# USB.net
KiCad netlist of a schematic drawn in Altium Designer
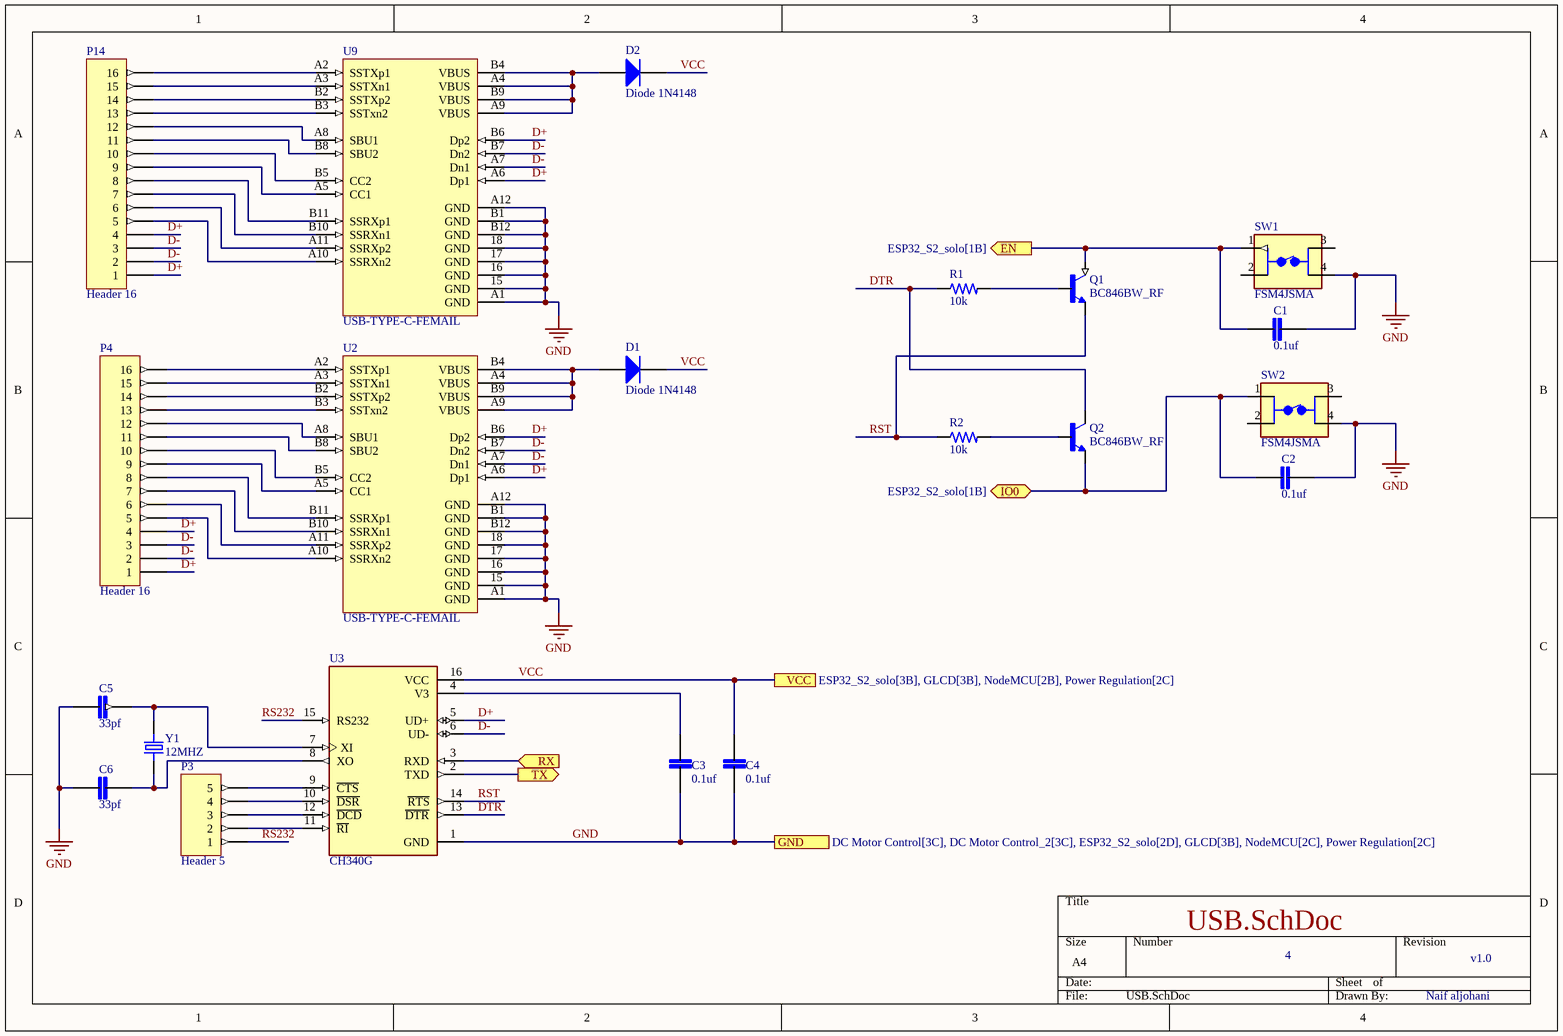
[diagram p0: USB.SchDoc]

(export (version "E")
  (design (tool "Eeschema 10.0.6"))
  (components
    (comp (ref "C1")
      (value "0.1uf")
      (footprint "CAPC2012X140N")
      (description "120PF 100V 10% 0805")
      (fields (field (name "MF") "{'manufacturer': u'AVX'}") (field (name "MP") "LD051A121KAB2A"))
      (libsource (lib "SnapEDA_Library") (part "LD051A121KAB2A"))
    )
    (comp (ref "C2")
      (value "0.1uf")
      (footprint "CAPC2012X140N")
      (description "120PF 100V 10% 0805")
      (fields (field (name "MF") "{'manufacturer': u'AVX'}") (field (name "MP") "LD051A121KAB2A"))
      (libsource (lib "SnapEDA_Library") (part "LD051A121KAB2A"))
    )
    (comp (ref "C3")
      (value "0.1uf")
      (footprint "CAPC2012X140N")
      (description "120PF 100V 10% 0805")
      (fields (field (name "MF") "{'manufacturer': u'AVX'}") (field (name "MP") "LD051A121KAB2A"))
      (libsource (lib "") (part "LD051A121KAB2A_1"))
    )
    (comp (ref "C4")
      (value "0.1uf")
      (footprint "CAPC2012X140N")
      (description "120PF 100V 10% 0805")
      (fields (field (name "MF") "{'manufacturer': u'AVX'}") (field (name "MP") "LD051A121KAB2A"))
      (libsource (lib "") (part "LD051A121KAB2A_1"))
    )
    (comp (ref "C5")
      (value "33pf")
      (footprint "CAPC2012X140N")
      (description "120PF 100V 10% 0805")
      (fields (field (name "MF") "{'manufacturer': u'AVX'}") (field (name "MP") "LD051A121KAB2A"))
      (libsource (lib "") (part "LD051A121KAB2A_3"))
    )
    (comp (ref "C6")
      (value "33pf")
      (footprint "CAPC2012X140N")
      (description "120PF 100V 10% 0805")
      (fields (field (name "MF") "{'manufacturer': u'AVX'}") (field (name "MP") "LD051A121KAB2A"))
      (libsource (lib "") (part "LD051A121KAB2A_2"))
    )
    (comp (ref "D1")
      (value "Diode 1N4148")
      (footprint "DO-35")
      (description "High Conductance Fast Diode")
      (fields (field (name "PUBLISHER") "Altium Limited"))
      (libsource (lib "Miscellaneous Devices") (part "Diode 1N4148"))
    )
    (comp (ref "D2")
      (value "Diode 1N4148")
      (footprint "DO-35")
      (description "High Conductance Fast Diode")
      (fields (field (name "PUBLISHER") "Altium Limited"))
      (libsource (lib "Miscellaneous Devices") (part "Diode 1N4148"))
    )
    (comp (ref "P3")
      (value "Header 5")
      (footprint "HDR1X5")
      (description "Header, 5-Pin")
      (fields (field (name "PUBLISHER") "Altium Limited"))
      (libsource (lib "Miscellaneous Connectors") (part "Header 5"))
    )
    (comp (ref "P4")
      (value "Header 16")
      (footprint "HDR1X16")
      (description "Header, 16-Pin")
      (fields (field (name "PUBLISHER") "Altium Limited"))
      (libsource (lib "Miscellaneous Connectors") (part "Header 16"))
    )
    (comp (ref "P14")
      (value "Header 16")
      (footprint "HDR1X16")
      (description "Header, 16-Pin")
      (fields (field (name "PUBLISHER") "Altium Limited"))
      (libsource (lib "Miscellaneous Connectors") (part "Header 16"))
    )
    (comp (ref "Q1")
      (value "BC846BW_RF")
      (footprint "TRANS_BC846BW_RF")
      (fields (field (name "MF") "{'manufacturer': u'Taiwan Semiconductor'}"))
      (libsource (lib "SnapEDA_Library") (part "BC846BW_RF"))
    )
    (comp (ref "Q2")
      (value "BC846BW_RF")
      (footprint "TRANS_BC846BW_RF")
      (fields (field (name "MF") "{'manufacturer': u'Taiwan Semiconductor'}"))
      (libsource (lib "SnapEDA_Library") (part "BC846BW_RF"))
    )
    (comp (ref "R1")
      (value "10k")
      (footprint "RESC3115X65N")
      (description "RL73H 2B R43 1% 10 RL")
      (fields (field (name "MF") "{'manufacturer': u'TE Connectivity'}") (field (name "MP") "1-1879462-4"))
      (libsource (lib "SnapEDA_Library") (part "1-1879462-4"))
    )
    (comp (ref "R2")
      (value "10k")
      (footprint "RESC3115X65N")
      (description "RL73H 2B R43 1% 10 RL")
      (fields (field (name "MF") "{'manufacturer': u'TE Connectivity'}") (field (name "MP") "1-1879462-4"))
      (libsource (lib "SnapEDA_Library") (part "1-1879462-4"))
    )
    (comp (ref "SW1")
      (value "FSM4JSMA")
      (footprint "TE_FSM4JSMA")
      (description "Switch Tactile OFF (ON) SPST Round Button Gull Wing 0.05A 24VDC 2.6N SMD T/R")
      (fields (field (name "MF") "{'manufacturer': u'TE Connectivity'}"))
      (libsource (lib "SnapEDA_Library") (part "FSM4JSMA"))
    )
    (comp (ref "SW2")
      (value "FSM4JSMA")
      (footprint "TE_FSM4JSMA")
      (description "Switch Tactile OFF (ON) SPST Round Button Gull Wing 0.05A 24VDC 2.6N SMD T/R")
      (fields (field (name "MF") "{'manufacturer': u'TE Connectivity'}"))
      (libsource (lib "SnapEDA_Library") (part "FSM4JSMA"))
    )
    (comp (ref "U2")
      (value "USB-TYPE-C-FEMAIL")
      (footprint "C5156605")
      (libsource (lib "Schlib2") (part "USB-TYPE-C-FEMAIL"))
    )
    (comp (ref "U3")
      (value "CH340G")
      (footprint "SOIC127P600X180-16N")
      (fields (field (name "MF") "{'manufacturer': u'WCH'}"))
      (libsource (lib "SnapEDA_Library") (part "CH340G"))
    )
    (comp (ref "U9")
      (value "USB-TYPE-C-FEMAIL")
      (footprint "C5156605")
      (libsource (lib "Schlib2") (part "USB-TYPE-C-FEMAIL"))
    )
    (comp (ref "Y1")
      (value "12MHZ")
      (footprint "XTAL_ECS-51-S-1")
      (fields (field (name "MF") "{'manufacturer': u'ECS'}") (field (name "MP") "ECS-51-S-1"))
      (libsource (lib "SnapEDA_Library") (part "ECS-51-S-1"))
    )
  )
  (nets
    (net (code "1") (name "/D+") (class "Default")
      (node (ref "P14") (pin "1") (pinfunction "1_1") (pintype "passive"))
      (node (ref "P14") (pin "4") (pinfunction "4_4") (pintype "passive"))
      (node (ref "P4") (pin "1") (pinfunction "1_1") (pintype "passive"))
      (node (ref "P4") (pin "4") (pinfunction "4_4") (pintype "passive"))
      (node (ref "U2") (pin "A6") (pinfunction "Dp1_A6") (pintype "input"))
      (node (ref "U2") (pin "B6") (pinfunction "Dp2_B6") (pintype "input"))
      (node (ref "U3") (pin "5") (pinfunction "UD+_5") (pintype "bidirectional"))
      (node (ref "U9") (pin "A6") (pinfunction "Dp1_A6") (pintype "input"))
      (node (ref "U9") (pin "B6") (pinfunction "Dp2_B6") (pintype "input"))
    )
    (net (code "2") (name "/D-") (class "Default")
      (node (ref "P14") (pin "2") (pinfunction "2_2") (pintype "passive"))
      (node (ref "P14") (pin "3") (pinfunction "3_3") (pintype "passive"))
      (node (ref "P4") (pin "2") (pinfunction "2_2") (pintype "passive"))
      (node (ref "P4") (pin "3") (pinfunction "3_3") (pintype "passive"))
      (node (ref "U2") (pin "A7") (pinfunction "Dn1_A7") (pintype "input"))
      (node (ref "U2") (pin "B7") (pinfunction "Dn2_B7") (pintype "input"))
      (node (ref "U3") (pin "6") (pinfunction "UD-_6") (pintype "bidirectional"))
      (node (ref "U9") (pin "A7") (pinfunction "Dn1_A7") (pintype "input"))
      (node (ref "U9") (pin "B7") (pinfunction "Dn2_B7") (pintype "input"))
    )
    (net (code "3") (name "/DTR") (class "Default")
      (node (ref "Q2") (pin "3") (pinfunction "C_3") (pintype "input"))
      (node (ref "R1") (pin "1") (pinfunction "1_1") (pintype "passive"))
      (node (ref "U3") (pin "13") (pinfunction "~{DTR}_13") (pintype "output"))
    )
    (net (code "4") (name "/EN") (class "Default")
      (node (ref "C1") (pin "1") (pinfunction "1_1") (pintype "passive"))
      (node (ref "Q1") (pin "3") (pinfunction "C_3") (pintype "input"))
      (node (ref "SW1") (pin "1") (pinfunction "1_1") (pintype "output"))
    )
    (net (code "5") (name "/IO0") (class "Default")
      (node (ref "C2") (pin "1") (pinfunction "1_1") (pintype "passive"))
      (node (ref "Q2") (pin "2") (pinfunction "E_2") (pintype "passive"))
      (node (ref "SW2") (pin "1") (pinfunction "1_1") (pintype "output"))
    )
    (net (code "6") (name "/RS232") (class "Default")
      (node (ref "P3") (pin "1") (pinfunction "1_1") (pintype "output"))
      (node (ref "U3") (pin "15") (pinfunction "RS232_15") (pintype "input"))
    )
    (net (code "7") (name "/RST") (class "Default")
      (node (ref "Q1") (pin "2") (pinfunction "E_2") (pintype "passive"))
      (node (ref "R2") (pin "1") (pinfunction "1_1") (pintype "passive"))
      (node (ref "U3") (pin "14") (pinfunction "~{RTS}_14") (pintype "output"))
    )
    (net (code "8") (name "/RX") (class "Default")
      (node (ref "U3") (pin "3") (pinfunction "RXD_3") (pintype "input"))
    )
    (net (code "9") (name "/TX") (class "Default")
      (node (ref "U3") (pin "2") (pinfunction "TXD_2") (pintype "output"))
    )
    (net (code "10") (name "/VCC") (class "Default")
      (node (ref "C4") (pin "2") (pinfunction "2_2") (pintype "passive"))
      (node (ref "D1") (pin "2") (pinfunction "K_2") (pintype "passive"))
      (node (ref "D2") (pin "2") (pinfunction "K_2") (pintype "passive"))
      (node (ref "U3") (pin "16") (pinfunction "VCC_16") (pintype "power_in"))
    )
    (net (code "11") (name "GND") (class "Default")
      (node (ref "C1") (pin "2") (pinfunction "2_2") (pintype "passive"))
      (node (ref "C2") (pin "2") (pinfunction "2_2") (pintype "passive"))
      (node (ref "C3") (pin "1") (pinfunction "1_1") (pintype "passive"))
      (node (ref "C4") (pin "1") (pinfunction "1_1") (pintype "passive"))
      (node (ref "C5") (pin "2") (pinfunction "2_2") (pintype "passive"))
      (node (ref "C6") (pin "2") (pinfunction "2_2") (pintype "passive"))
      (node (ref "SW1") (pin "4") (pinfunction "4_4") (pintype "passive"))
      (node (ref "SW2") (pin "4") (pinfunction "4_4") (pintype "passive"))
      (node (ref "U2") (pin "15") (pinfunction "GND_15") (pintype "power_in"))
      (node (ref "U2") (pin "16") (pinfunction "GND_16") (pintype "power_in"))
      (node (ref "U2") (pin "17") (pinfunction "GND_17") (pintype "power_in"))
      (node (ref "U2") (pin "18") (pinfunction "GND_18") (pintype "power_in"))
      (node (ref "U2") (pin "A1") (pinfunction "GND_A1") (pintype "power_in"))
      (node (ref "U2") (pin "A12") (pinfunction "GND_A12") (pintype "power_in"))
      (node (ref "U2") (pin "B1") (pinfunction "GND_B1") (pintype "power_in"))
      (node (ref "U2") (pin "B12") (pinfunction "GND_B12") (pintype "power_in"))
      (node (ref "U3") (pin "1") (pinfunction "GND_1") (pintype "power_in"))
      (node (ref "U9") (pin "15") (pinfunction "GND_15") (pintype "power_in"))
      (node (ref "U9") (pin "16") (pinfunction "GND_16") (pintype "power_in"))
      (node (ref "U9") (pin "17") (pinfunction "GND_17") (pintype "power_in"))
      (node (ref "U9") (pin "18") (pinfunction "GND_18") (pintype "power_in"))
      (node (ref "U9") (pin "A1") (pinfunction "GND_A1") (pintype "power_in"))
      (node (ref "U9") (pin "A12") (pinfunction "GND_A12") (pintype "power_in"))
      (node (ref "U9") (pin "B1") (pinfunction "GND_B1") (pintype "power_in"))
      (node (ref "U9") (pin "B12") (pinfunction "GND_B12") (pintype "power_in"))
    )
    (net (code "12") (name "Net-(D1-A)") (class "Default")
      (node (ref "D1") (pin "1") (pinfunction "A_1") (pintype "passive"))
      (node (ref "U2") (pin "A4") (pinfunction "VBUS_A4") (pintype "power_in"))
      (node (ref "U2") (pin "A9") (pinfunction "VBUS_A9") (pintype "power_in"))
      (node (ref "U2") (pin "B4") (pinfunction "VBUS_B4") (pintype "power_in"))
      (node (ref "U2") (pin "B9") (pinfunction "VBUS_B9") (pintype "power_in"))
    )
    (net (code "13") (name "Net-(D2-A)") (class "Default")
      (node (ref "D2") (pin "1") (pinfunction "A_1") (pintype "passive"))
      (node (ref "U9") (pin "A4") (pinfunction "VBUS_A4") (pintype "power_in"))
      (node (ref "U9") (pin "A9") (pinfunction "VBUS_A9") (pintype "power_in"))
      (node (ref "U9") (pin "B4") (pinfunction "VBUS_B4") (pintype "power_in"))
      (node (ref "U9") (pin "B9") (pinfunction "VBUS_B9") (pintype "power_in"))
    )
    (net (code "14") (name "Net-(Q1-B)") (class "Default")
      (node (ref "Q1") (pin "1") (pinfunction "B_1") (pintype "passive"))
      (node (ref "R1") (pin "2") (pinfunction "2_2") (pintype "passive"))
    )
    (net (code "15") (name "Net-(Q2-B)") (class "Default")
      (node (ref "Q2") (pin "1") (pinfunction "B_1") (pintype "passive"))
      (node (ref "R2") (pin "2") (pinfunction "2_2") (pintype "passive"))
    )
    (net (code "16") (name "Net-(U2-CC1)") (class "Default")
      (node (ref "P4") (pin "9") (pinfunction "9_9") (pintype "output"))
      (node (ref "U2") (pin "A5") (pinfunction "CC1_A5") (pintype "input"))
    )
    (net (code "17") (name "Net-(U2-CC2)") (class "Default")
      (node (ref "P4") (pin "10") (pinfunction "10_10") (pintype "output"))
      (node (ref "U2") (pin "B5") (pinfunction "CC2_B5") (pintype "input"))
    )
    (net (code "18") (name "Net-(U2-SBU1)") (class "Default")
      (node (ref "P4") (pin "12") (pinfunction "12_12") (pintype "output"))
      (node (ref "U2") (pin "A8") (pinfunction "SBU1_A8") (pintype "input"))
    )
    (net (code "19") (name "Net-(U2-SBU2)") (class "Default")
      (node (ref "P4") (pin "11") (pinfunction "11_11") (pintype "output"))
      (node (ref "U2") (pin "B8") (pinfunction "SBU2_B8") (pintype "input"))
    )
    (net (code "20") (name "Net-(U2-SSRXn1)") (class "Default")
      (node (ref "P4") (pin "7") (pinfunction "7_7") (pintype "output"))
      (node (ref "U2") (pin "B10") (pinfunction "SSRXn1_B10") (pintype "input"))
    )
    (net (code "21") (name "Net-(U2-SSRXn2)") (class "Default")
      (node (ref "P4") (pin "5") (pinfunction "5_5") (pintype "output"))
      (node (ref "U2") (pin "A10") (pinfunction "SSRXn2_A10") (pintype "input"))
    )
    (net (code "22") (name "Net-(U2-SSRXp1)") (class "Default")
      (node (ref "P4") (pin "8") (pinfunction "8_8") (pintype "output"))
      (node (ref "U2") (pin "B11") (pinfunction "SSRXp1_B11") (pintype "input"))
    )
    (net (code "23") (name "Net-(U2-SSRXp2)") (class "Default")
      (node (ref "P4") (pin "6") (pinfunction "6_6") (pintype "output"))
      (node (ref "U2") (pin "A11") (pinfunction "SSRXp2_A11") (pintype "input"))
    )
    (net (code "24") (name "Net-(U2-SSTXn1)") (class "Default")
      (node (ref "P4") (pin "15") (pinfunction "15_15") (pintype "output"))
      (node (ref "U2") (pin "A3") (pinfunction "SSTXn1_A3") (pintype "input"))
    )
    (net (code "25") (name "Net-(U2-SSTXp1)") (class "Default")
      (node (ref "P4") (pin "16") (pinfunction "16_16") (pintype "output"))
      (node (ref "U2") (pin "A2") (pinfunction "SSTXp1_A2") (pintype "input"))
    )
    (net (code "26") (name "Net-(U2-SSTXp2)") (class "Default")
      (node (ref "P4") (pin "14") (pinfunction "14_14") (pintype "output"))
      (node (ref "U2") (pin "B2") (pinfunction "SSTXp2_B2") (pintype "input"))
    )
    (net (code "27") (name "Net-(U2-SSTxn2)") (class "Default")
      (node (ref "P4") (pin "13") (pinfunction "13_13") (pintype "output"))
      (node (ref "U2") (pin "B3") (pinfunction "SSTxn2_B3") (pintype "input"))
    )
    (net (code "28") (name "Net-(U3-V3)") (class "Default")
      (node (ref "C3") (pin "2") (pinfunction "2_2") (pintype "passive"))
      (node (ref "U3") (pin "4") (pinfunction "V3_4") (pintype "power_in"))
    )
    (net (code "29") (name "Net-(U3-XI)") (class "Default")
      (node (ref "C5") (pin "1") (pinfunction "1_1") (pintype "output"))
      (node (ref "U3") (pin "7") (pinfunction "XI_7") (pintype "input"))
      (node (ref "Y1") (pin "2") (pinfunction "2_2") (pintype "passive"))
    )
    (net (code "30") (name "Net-(U3-XO)") (class "Default")
      (node (ref "C6") (pin "1") (pinfunction "1_1") (pintype "passive"))
      (node (ref "U3") (pin "8") (pinfunction "XO_8") (pintype "output"))
      (node (ref "Y1") (pin "1") (pinfunction "1_1") (pintype "passive"))
    )
    (net (code "31") (name "Net-(U3-~{CTS})") (class "Default")
      (node (ref "P3") (pin "5") (pinfunction "5_5") (pintype "output"))
      (node (ref "U3") (pin "9") (pinfunction "~{CTS}_9") (pintype "input"))
    )
    (net (code "32") (name "Net-(U3-~{DCD})") (class "Default")
      (node (ref "P3") (pin "3") (pinfunction "3_3") (pintype "output"))
      (node (ref "U3") (pin "12") (pinfunction "~{DCD}_12") (pintype "input"))
    )
    (net (code "33") (name "Net-(U3-~{DSR})") (class "Default")
      (node (ref "P3") (pin "4") (pinfunction "4_4") (pintype "output"))
      (node (ref "U3") (pin "10") (pinfunction "~{DSR}_10") (pintype "input"))
    )
    (net (code "34") (name "Net-(U3-~{RI})") (class "Default")
      (node (ref "P3") (pin "2") (pinfunction "2_2") (pintype "output"))
      (node (ref "U3") (pin "11") (pinfunction "~{RI}_11") (pintype "input"))
    )
    (net (code "35") (name "Net-(U9-CC1)") (class "Default")
      (node (ref "P14") (pin "9") (pinfunction "9_9") (pintype "output"))
      (node (ref "U9") (pin "A5") (pinfunction "CC1_A5") (pintype "input"))
    )
    (net (code "36") (name "Net-(U9-CC2)") (class "Default")
      (node (ref "P14") (pin "10") (pinfunction "10_10") (pintype "output"))
      (node (ref "U9") (pin "B5") (pinfunction "CC2_B5") (pintype "input"))
    )
    (net (code "37") (name "Net-(U9-SBU1)") (class "Default")
      (node (ref "P14") (pin "12") (pinfunction "12_12") (pintype "output"))
      (node (ref "U9") (pin "A8") (pinfunction "SBU1_A8") (pintype "input"))
    )
    (net (code "38") (name "Net-(U9-SBU2)") (class "Default")
      (node (ref "P14") (pin "11") (pinfunction "11_11") (pintype "output"))
      (node (ref "U9") (pin "B8") (pinfunction "SBU2_B8") (pintype "input"))
    )
    (net (code "39") (name "Net-(U9-SSRXn1)") (class "Default")
      (node (ref "P14") (pin "7") (pinfunction "7_7") (pintype "output"))
      (node (ref "U9") (pin "B10") (pinfunction "SSRXn1_B10") (pintype "input"))
    )
    (net (code "40") (name "Net-(U9-SSRXn2)") (class "Default")
      (node (ref "P14") (pin "5") (pinfunction "5_5") (pintype "output"))
      (node (ref "U9") (pin "A10") (pinfunction "SSRXn2_A10") (pintype "input"))
    )
    (net (code "41") (name "Net-(U9-SSRXp1)") (class "Default")
      (node (ref "P14") (pin "8") (pinfunction "8_8") (pintype "output"))
      (node (ref "U9") (pin "B11") (pinfunction "SSRXp1_B11") (pintype "input"))
    )
    (net (code "42") (name "Net-(U9-SSRXp2)") (class "Default")
      (node (ref "P14") (pin "6") (pinfunction "6_6") (pintype "output"))
      (node (ref "U9") (pin "A11") (pinfunction "SSRXp2_A11") (pintype "input"))
    )
    (net (code "43") (name "Net-(U9-SSTXn1)") (class "Default")
      (node (ref "P14") (pin "15") (pinfunction "15_15") (pintype "output"))
      (node (ref "U9") (pin "A3") (pinfunction "SSTXn1_A3") (pintype "input"))
    )
    (net (code "44") (name "Net-(U9-SSTXp1)") (class "Default")
      (node (ref "P14") (pin "16") (pinfunction "16_16") (pintype "output"))
      (node (ref "U9") (pin "A2") (pinfunction "SSTXp1_A2") (pintype "input"))
    )
    (net (code "45") (name "Net-(U9-SSTXp2)") (class "Default")
      (node (ref "P14") (pin "14") (pinfunction "14_14") (pintype "output"))
      (node (ref "U9") (pin "B2") (pinfunction "SSTXp2_B2") (pintype "input"))
    )
    (net (code "46") (name "Net-(U9-SSTxn2)") (class "Default")
      (node (ref "P14") (pin "13") (pinfunction "13_13") (pintype "output"))
      (node (ref "U9") (pin "B3") (pinfunction "SSTxn2_B3") (pintype "input"))
    )
    (net (code "47") (name "unconnected-(SW1-Pad2)") (class "Default")
      (node (ref "SW1") (pin "2") (pinfunction "2_2") (pintype "passive"))
    )
    (net (code "48") (name "unconnected-(SW1-Pad3)") (class "Default")
      (node (ref "SW1") (pin "3") (pinfunction "3_3") (pintype "passive"))
    )
    (net (code "49") (name "unconnected-(SW2-Pad2)") (class "Default")
      (node (ref "SW2") (pin "2") (pinfunction "2_2") (pintype "passive"))
    )
    (net (code "50") (name "unconnected-(SW2-Pad3)") (class "Default")
      (node (ref "SW2") (pin "3") (pinfunction "3_3") (pintype "passive"))
    )
  )
)
